# MacroBoard.net
KiCad netlist of a schematic drawn in EAGLE
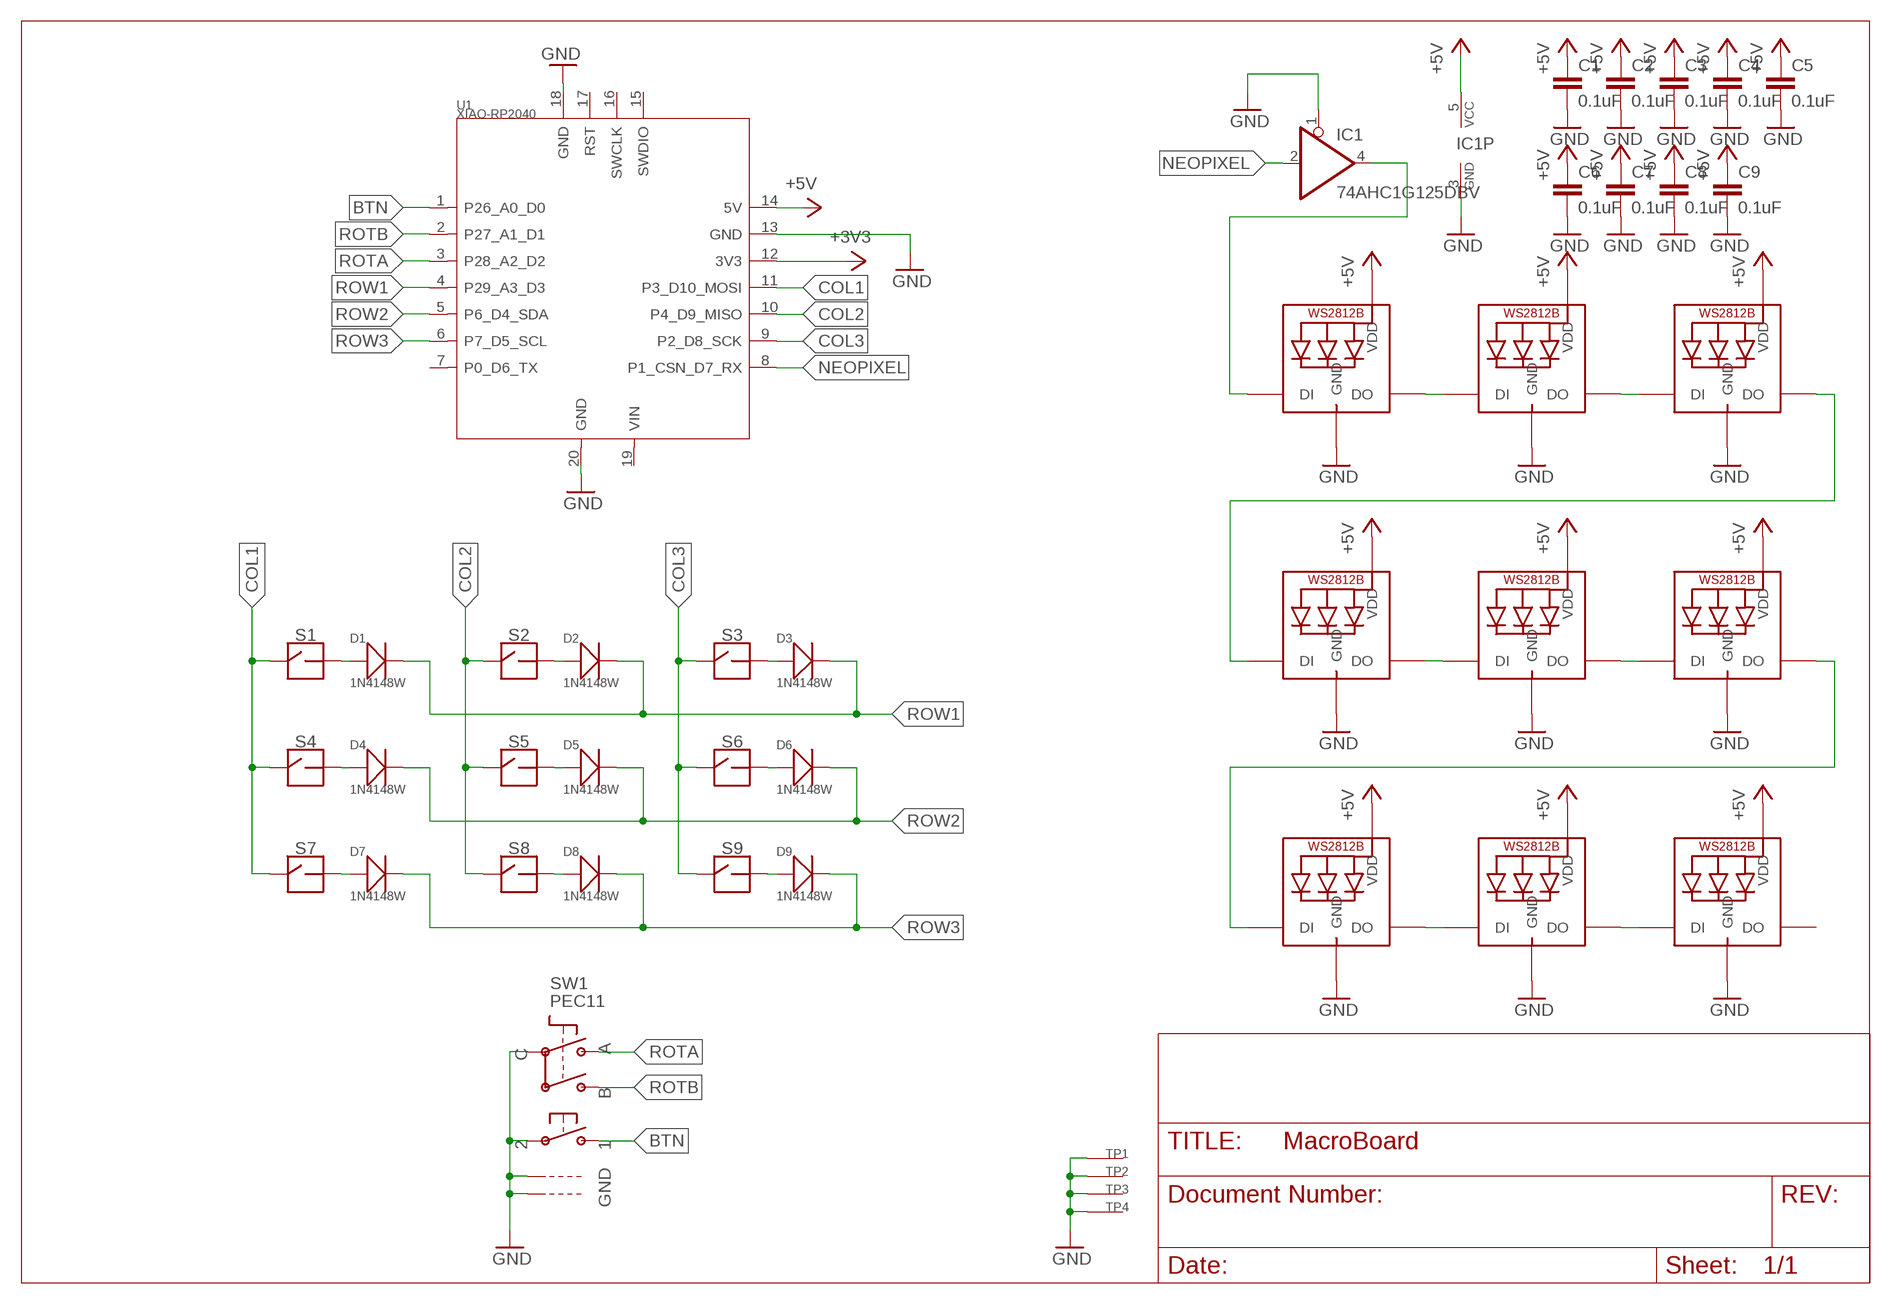
[diagram p0: schematic, sheet 1]

(export (version "E")
  (design (tool "Eeschema 10.0.6"))
  (components
    (comp (ref "C1")
      (value "0.1uF")
      (footprint "eagle-import:C0805K")
      (libsource (lib "eagle-import") (part "C-EUC0805K"))
    )
    (comp (ref "C2")
      (value "0.1uF")
      (footprint "eagle-import:C0805K")
      (libsource (lib "eagle-import") (part "C-EUC0805K"))
    )
    (comp (ref "C3")
      (value "0.1uF")
      (footprint "eagle-import:C0805K")
      (libsource (lib "eagle-import") (part "C-EUC0805K"))
    )
    (comp (ref "C4")
      (value "0.1uF")
      (footprint "eagle-import:C0805K")
      (libsource (lib "eagle-import") (part "C-EUC0805K"))
    )
    (comp (ref "C5")
      (value "0.1uF")
      (footprint "eagle-import:C0805K")
      (libsource (lib "eagle-import") (part "C-EUC0805K"))
    )
    (comp (ref "C6")
      (value "0.1uF")
      (footprint "eagle-import:C0805K")
      (libsource (lib "eagle-import") (part "C-EUC0805K"))
    )
    (comp (ref "C7")
      (value "0.1uF")
      (footprint "eagle-import:C0805K")
      (libsource (lib "eagle-import") (part "C-EUC0805K"))
    )
    (comp (ref "C8")
      (value "0.1uF")
      (footprint "eagle-import:C0805K")
      (libsource (lib "eagle-import") (part "C-EUC0805K"))
    )
    (comp (ref "C9")
      (value "0.1uF")
      (footprint "eagle-import:C0805K")
      (libsource (lib "eagle-import") (part "C-EUC0805K"))
    )
    (comp (ref "D1")
      (value "1N4148W")
      (footprint "eagle-import:SOD-123")
      (fields (field (name "MPN") "B5819W"))
      (libsource (lib "eagle-import") (part "SMD-DIODE-SCHOTTKY-20V-1A(SOD-123)"))
    )
    (comp (ref "D2")
      (value "1N4148W")
      (footprint "eagle-import:SOD-123")
      (fields (field (name "MPN") "B5819W"))
      (libsource (lib "eagle-import") (part "SMD-DIODE-SCHOTTKY-20V-1A(SOD-123)"))
    )
    (comp (ref "D3")
      (value "1N4148W")
      (footprint "eagle-import:SOD-123")
      (fields (field (name "MPN") "B5819W"))
      (libsource (lib "eagle-import") (part "SMD-DIODE-SCHOTTKY-20V-1A(SOD-123)"))
    )
    (comp (ref "D4")
      (value "1N4148W")
      (footprint "eagle-import:SOD-123")
      (fields (field (name "MPN") "B5819W"))
      (libsource (lib "eagle-import") (part "SMD-DIODE-SCHOTTKY-20V-1A(SOD-123)"))
    )
    (comp (ref "D5")
      (value "1N4148W")
      (footprint "eagle-import:SOD-123")
      (fields (field (name "MPN") "B5819W"))
      (libsource (lib "eagle-import") (part "SMD-DIODE-SCHOTTKY-20V-1A(SOD-123)"))
    )
    (comp (ref "D6")
      (value "1N4148W")
      (footprint "eagle-import:SOD-123")
      (fields (field (name "MPN") "B5819W"))
      (libsource (lib "eagle-import") (part "SMD-DIODE-SCHOTTKY-20V-1A(SOD-123)"))
    )
    (comp (ref "D7")
      (value "1N4148W")
      (footprint "eagle-import:SOD-123")
      (fields (field (name "MPN") "B5819W"))
      (libsource (lib "eagle-import") (part "SMD-DIODE-SCHOTTKY-20V-1A(SOD-123)"))
    )
    (comp (ref "D8")
      (value "1N4148W")
      (footprint "eagle-import:SOD-123")
      (fields (field (name "MPN") "B5819W"))
      (libsource (lib "eagle-import") (part "SMD-DIODE-SCHOTTKY-20V-1A(SOD-123)"))
    )
    (comp (ref "D9")
      (value "1N4148W")
      (footprint "eagle-import:SOD-123")
      (fields (field (name "MPN") "B5819W"))
      (libsource (lib "eagle-import") (part "SMD-DIODE-SCHOTTKY-20V-1A(SOD-123)"))
    )
    (comp (ref "IC1")
      (value "74AHC1G125DBV")
      (footprint "eagle-import:SOT23-5")
      (fields (field (name "SPICEPREFIX") "J"))
      (libsource (lib "eagle-import") (part "741G125DBVAHC"))
    )
    (comp (ref "LED1")
      (value "WS2812B_SK6812E")
      (footprint "eagle-import:NEO3535_REVERSE")
      (libsource (lib "eagle-import") (part "WS2812B_SK6812E"))
    )
    (comp (ref "LED2")
      (value "WS2812B_SK6812E")
      (footprint "eagle-import:NEO3535_REVERSE")
      (libsource (lib "eagle-import") (part "WS2812B_SK6812E"))
    )
    (comp (ref "LED3")
      (value "WS2812B_SK6812E")
      (footprint "eagle-import:NEO3535_REVERSE")
      (libsource (lib "eagle-import") (part "WS2812B_SK6812E"))
    )
    (comp (ref "LED4")
      (value "WS2812B_SK6812E")
      (footprint "eagle-import:NEO3535_REVERSE")
      (libsource (lib "eagle-import") (part "WS2812B_SK6812E"))
    )
    (comp (ref "LED5")
      (value "WS2812B_SK6812E")
      (footprint "eagle-import:NEO3535_REVERSE")
      (libsource (lib "eagle-import") (part "WS2812B_SK6812E"))
    )
    (comp (ref "LED6")
      (value "WS2812B_SK6812E")
      (footprint "eagle-import:NEO3535_REVERSE")
      (libsource (lib "eagle-import") (part "WS2812B_SK6812E"))
    )
    (comp (ref "LED7")
      (value "WS2812B_SK6812E")
      (footprint "eagle-import:NEO3535_REVERSE")
      (libsource (lib "eagle-import") (part "WS2812B_SK6812E"))
    )
    (comp (ref "LED8")
      (value "WS2812B_SK6812E")
      (footprint "eagle-import:NEO3535_REVERSE")
      (libsource (lib "eagle-import") (part "WS2812B_SK6812E"))
    )
    (comp (ref "LED9")
      (value "WS2812B_SK6812E")
      (footprint "eagle-import:NEO3535_REVERSE")
      (libsource (lib "eagle-import") (part "WS2812B_SK6812E"))
    )
    (comp (ref "S1")
      (value "SOCKET")
      (footprint "eagle-import:KAILH_SOCKET")
      (libsource (lib "eagle-import") (part "KBD_SWITCH_KAILH_SOCKETBOX_JADE_KAILH_SOCKET"))
    )
    (comp (ref "S2")
      (value "SOCKET")
      (footprint "eagle-import:KAILH_SOCKET")
      (libsource (lib "eagle-import") (part "KBD_SWITCH_KAILH_SOCKETBOX_JADE_KAILH_SOCKET"))
    )
    (comp (ref "S3")
      (value "SOCKET")
      (footprint "eagle-import:KAILH_SOCKET")
      (libsource (lib "eagle-import") (part "KBD_SWITCH_KAILH_SOCKETBOX_JADE_KAILH_SOCKET"))
    )
    (comp (ref "S4")
      (value "SOCKET")
      (footprint "eagle-import:KAILH_SOCKET")
      (libsource (lib "eagle-import") (part "KBD_SWITCH_KAILH_SOCKETBOX_JADE_KAILH_SOCKET"))
    )
    (comp (ref "S5")
      (value "SOCKET")
      (footprint "eagle-import:KAILH_SOCKET")
      (libsource (lib "eagle-import") (part "KBD_SWITCH_KAILH_SOCKETBOX_JADE_KAILH_SOCKET"))
    )
    (comp (ref "S6")
      (value "SOCKET")
      (footprint "eagle-import:KAILH_SOCKET")
      (libsource (lib "eagle-import") (part "KBD_SWITCH_KAILH_SOCKETBOX_JADE_KAILH_SOCKET"))
    )
    (comp (ref "S7")
      (value "SOCKET")
      (footprint "eagle-import:KAILH_SOCKET")
      (libsource (lib "eagle-import") (part "KBD_SWITCH_KAILH_SOCKETBOX_JADE_KAILH_SOCKET"))
    )
    (comp (ref "S8")
      (value "SOCKET")
      (footprint "eagle-import:KAILH_SOCKET")
      (libsource (lib "eagle-import") (part "KBD_SWITCH_KAILH_SOCKETBOX_JADE_KAILH_SOCKET"))
    )
    (comp (ref "S9")
      (value "SOCKET")
      (footprint "eagle-import:KAILH_SOCKET")
      (libsource (lib "eagle-import") (part "KBD_SWITCH_KAILH_SOCKETBOX_JADE_KAILH_SOCKET"))
    )
    (comp (ref "SW1")
      (value "PEC11")
      (footprint "eagle-import:PEC11+SWITCH")
      (libsource (lib "eagle-import") (part "ENCODER_PLUS_SWITCH_PEC11_BOURNS"))
    )
    (comp (ref "TP1")
      (value "SEWTAP_SMTNUTM3")
      (footprint "eagle-import:SMT_NUT_3MM")
      (libsource (lib "eagle-import") (part "SEWTAP_SMTNUTM3"))
    )
    (comp (ref "TP2")
      (value "SEWTAP_SMTNUTM3")
      (footprint "eagle-import:SMT_NUT_3MM")
      (libsource (lib "eagle-import") (part "SEWTAP_SMTNUTM3"))
    )
    (comp (ref "TP3")
      (value "SEWTAP_SMTNUTM3")
      (footprint "eagle-import:SMT_NUT_3MM")
      (libsource (lib "eagle-import") (part "SEWTAP_SMTNUTM3"))
    )
    (comp (ref "TP4")
      (value "SEWTAP_SMTNUTM3")
      (footprint "eagle-import:SMT_NUT_3MM")
      (libsource (lib "eagle-import") (part "SEWTAP_SMTNUTM3"))
    )
    (comp (ref "U1")
      (value "XIAO-RP2040")
      (footprint "eagle-import:XIAO-SAMD21_RP2040-MODULE14P-2.54-21X17.8MM")
      (libsource (lib "eagle-import") (part "XIAO-RP2040"))
    )
  )
  (nets
    (net (code "1") (name "+3V3") (class "Default")
      (node (ref "U1") (pin "12") (pinfunction "3V3_12") (pintype "bidirectional"))
    )
    (net (code "2") (name "+5V") (class "Default")
      (node (ref "C1") (pin "1") (pinfunction "1_1") (pintype "passive"))
      (node (ref "C2") (pin "1") (pinfunction "1_1") (pintype "passive"))
      (node (ref "C3") (pin "1") (pinfunction "1_1") (pintype "passive"))
      (node (ref "C4") (pin "1") (pinfunction "1_1") (pintype "passive"))
      (node (ref "C5") (pin "1") (pinfunction "1_1") (pintype "passive"))
      (node (ref "C6") (pin "1") (pinfunction "1_1") (pintype "passive"))
      (node (ref "C7") (pin "1") (pinfunction "1_1") (pintype "passive"))
      (node (ref "C8") (pin "1") (pinfunction "1_1") (pintype "passive"))
      (node (ref "C9") (pin "1") (pinfunction "1_1") (pintype "passive"))
      (node (ref "IC1") (pin "5") (pinfunction "VCC_5") (pintype "power_in"))
      (node (ref "LED1") (pin "1-VDD") (pinfunction "VDD_1-VDD") (pintype "power_in"))
      (node (ref "LED2") (pin "1-VDD") (pinfunction "VDD_1-VDD") (pintype "power_in"))
      (node (ref "LED3") (pin "1-VDD") (pinfunction "VDD_1-VDD") (pintype "power_in"))
      (node (ref "LED4") (pin "1-VDD") (pinfunction "VDD_1-VDD") (pintype "power_in"))
      (node (ref "LED5") (pin "1-VDD") (pinfunction "VDD_1-VDD") (pintype "power_in"))
      (node (ref "LED6") (pin "1-VDD") (pinfunction "VDD_1-VDD") (pintype "power_in"))
      (node (ref "LED7") (pin "1-VDD") (pinfunction "VDD_1-VDD") (pintype "power_in"))
      (node (ref "LED8") (pin "1-VDD") (pinfunction "VDD_1-VDD") (pintype "power_in"))
      (node (ref "LED9") (pin "1-VDD") (pinfunction "VDD_1-VDD") (pintype "power_in"))
      (node (ref "U1") (pin "14") (pinfunction "5V_14") (pintype "bidirectional"))
    )
    (net (code "3") (name "BTN") (class "Default")
      (node (ref "SW1") (pin "P$1") (pinfunction "P$1_P$1") (pintype "passive"))
      (node (ref "U1") (pin "1") (pinfunction "P26_A0_D0_1") (pintype "bidirectional"))
    )
    (net (code "4") (name "COL1") (class "Default")
      (node (ref "S1") (pin "1") (pinfunction "1_1") (pintype "passive"))
      (node (ref "S4") (pin "1") (pinfunction "1_1") (pintype "passive"))
      (node (ref "S7") (pin "1") (pinfunction "1_1") (pintype "passive"))
      (node (ref "U1") (pin "11") (pinfunction "P3_D10_MOSI_11") (pintype "bidirectional"))
    )
    (net (code "5") (name "COL2") (class "Default")
      (node (ref "S2") (pin "1") (pinfunction "1_1") (pintype "passive"))
      (node (ref "S5") (pin "1") (pinfunction "1_1") (pintype "passive"))
      (node (ref "S8") (pin "1") (pinfunction "1_1") (pintype "passive"))
      (node (ref "U1") (pin "10") (pinfunction "P4_D9_MISO_10") (pintype "bidirectional"))
    )
    (net (code "6") (name "COL3") (class "Default")
      (node (ref "S3") (pin "1") (pinfunction "1_1") (pintype "passive"))
      (node (ref "S6") (pin "1") (pinfunction "1_1") (pintype "passive"))
      (node (ref "S9") (pin "1") (pinfunction "1_1") (pintype "passive"))
      (node (ref "U1") (pin "9") (pinfunction "P2_D8_SCK_9") (pintype "bidirectional"))
    )
    (net (code "7") (name "GND") (class "Default")
      (node (ref "C1") (pin "2") (pinfunction "2_2") (pintype "passive"))
      (node (ref "C2") (pin "2") (pinfunction "2_2") (pintype "passive"))
      (node (ref "C3") (pin "2") (pinfunction "2_2") (pintype "passive"))
      (node (ref "C4") (pin "2") (pinfunction "2_2") (pintype "passive"))
      (node (ref "C5") (pin "2") (pinfunction "2_2") (pintype "passive"))
      (node (ref "C6") (pin "2") (pinfunction "2_2") (pintype "passive"))
      (node (ref "C7") (pin "2") (pinfunction "2_2") (pintype "passive"))
      (node (ref "C8") (pin "2") (pinfunction "2_2") (pintype "passive"))
      (node (ref "C9") (pin "2") (pinfunction "2_2") (pintype "passive"))
      (node (ref "IC1") (pin "1") (pinfunction "OE_1") (pintype "input"))
      (node (ref "IC1") (pin "3") (pinfunction "GND_3") (pintype "power_in"))
      (node (ref "LED1") (pin "3-GND") (pinfunction "GND_3-GND") (pintype "power_in"))
      (node (ref "LED2") (pin "3-GND") (pinfunction "GND_3-GND") (pintype "power_in"))
      (node (ref "LED3") (pin "3-GND") (pinfunction "GND_3-GND") (pintype "power_in"))
      (node (ref "LED4") (pin "3-GND") (pinfunction "GND_3-GND") (pintype "power_in"))
      (node (ref "LED5") (pin "3-GND") (pinfunction "GND_3-GND") (pintype "power_in"))
      (node (ref "LED6") (pin "3-GND") (pinfunction "GND_3-GND") (pintype "power_in"))
      (node (ref "LED7") (pin "3-GND") (pinfunction "GND_3-GND") (pintype "power_in"))
      (node (ref "LED8") (pin "3-GND") (pinfunction "GND_3-GND") (pintype "power_in"))
      (node (ref "LED9") (pin "3-GND") (pinfunction "GND_3-GND") (pintype "power_in"))
      (node (ref "SW1") (pin "P$2") (pinfunction "P$2_P$2") (pintype "passive"))
      (node (ref "SW1") (pin "P$C") (pinfunction "P$C_P$C") (pintype "passive"))
      (node (ref "SW1") (pin "P$GND1") (pinfunction "P$GND1_P$GND1") (pintype "passive"))
      (node (ref "SW1") (pin "P$GND2") (pinfunction "P$GND2_P$GND2") (pintype "passive"))
      (node (ref "TP1") (pin "P$1") (pinfunction "SEW_P$1") (pintype "bidirectional"))
      (node (ref "TP2") (pin "P$1") (pinfunction "SEW_P$1") (pintype "bidirectional"))
      (node (ref "TP3") (pin "P$1") (pinfunction "SEW_P$1") (pintype "bidirectional"))
      (node (ref "TP4") (pin "P$1") (pinfunction "SEW_P$1") (pintype "bidirectional"))
      (node (ref "U1") (pin "13") (pinfunction "GND_13") (pintype "bidirectional"))
      (node (ref "U1") (pin "18") (pinfunction "GND_18") (pintype "bidirectional"))
      (node (ref "U1") (pin "20") (pinfunction "GND_20") (pintype "bidirectional"))
    )
    (net (code "8") (name "NEOPIXEL") (class "Default")
      (node (ref "IC1") (pin "2") (pinfunction "I_2") (pintype "input"))
      (node (ref "U1") (pin "8") (pinfunction "P1_CSN_D7_RX_8") (pintype "bidirectional"))
    )
    (net (code "9") (name "Net-(D1-Pad+)") (class "Default")
      (node (ref "D1") (pin "+") (pinfunction "+_+") (pintype "passive"))
      (node (ref "S1") (pin "2") (pinfunction "2_2") (pintype "passive"))
    )
    (net (code "10") (name "Net-(D2-Pad+)") (class "Default")
      (node (ref "D2") (pin "+") (pinfunction "+_+") (pintype "passive"))
      (node (ref "S2") (pin "2") (pinfunction "2_2") (pintype "passive"))
    )
    (net (code "11") (name "Net-(D3-Pad+)") (class "Default")
      (node (ref "D3") (pin "+") (pinfunction "+_+") (pintype "passive"))
      (node (ref "S3") (pin "2") (pinfunction "2_2") (pintype "passive"))
    )
    (net (code "12") (name "Net-(D4-Pad+)") (class "Default")
      (node (ref "D4") (pin "+") (pinfunction "+_+") (pintype "passive"))
      (node (ref "S4") (pin "2") (pinfunction "2_2") (pintype "passive"))
    )
    (net (code "13") (name "Net-(D5-Pad+)") (class "Default")
      (node (ref "D5") (pin "+") (pinfunction "+_+") (pintype "passive"))
      (node (ref "S5") (pin "2") (pinfunction "2_2") (pintype "passive"))
    )
    (net (code "14") (name "Net-(D6-Pad+)") (class "Default")
      (node (ref "D6") (pin "+") (pinfunction "+_+") (pintype "passive"))
      (node (ref "S6") (pin "2") (pinfunction "2_2") (pintype "passive"))
    )
    (net (code "15") (name "Net-(D7-Pad+)") (class "Default")
      (node (ref "D7") (pin "+") (pinfunction "+_+") (pintype "passive"))
      (node (ref "S7") (pin "2") (pinfunction "2_2") (pintype "passive"))
    )
    (net (code "16") (name "Net-(D8-Pad+)") (class "Default")
      (node (ref "D8") (pin "+") (pinfunction "+_+") (pintype "passive"))
      (node (ref "S8") (pin "2") (pinfunction "2_2") (pintype "passive"))
    )
    (net (code "17") (name "Net-(D9-Pad+)") (class "Default")
      (node (ref "D9") (pin "+") (pinfunction "+_+") (pintype "passive"))
      (node (ref "S9") (pin "2") (pinfunction "2_2") (pintype "passive"))
    )
    (net (code "18") (name "Net-(IC1A-O)") (class "Default")
      (node (ref "IC1") (pin "4") (pinfunction "O_4") (pintype "tri_state"))
      (node (ref "LED1") (pin "4-DIN") (pinfunction "DI_4-DIN") (pintype "input"))
    )
    (net (code "19") (name "Net-(LED1-DO)") (class "Default")
      (node (ref "LED1") (pin "2-DOUT") (pinfunction "DO_2-DOUT") (pintype "output"))
      (node (ref "LED2") (pin "4-DIN") (pinfunction "DI_4-DIN") (pintype "input"))
    )
    (net (code "20") (name "Net-(LED2-DO)") (class "Default")
      (node (ref "LED2") (pin "2-DOUT") (pinfunction "DO_2-DOUT") (pintype "output"))
      (node (ref "LED3") (pin "4-DIN") (pinfunction "DI_4-DIN") (pintype "input"))
    )
    (net (code "21") (name "Net-(LED3-DO)") (class "Default")
      (node (ref "LED3") (pin "2-DOUT") (pinfunction "DO_2-DOUT") (pintype "output"))
      (node (ref "LED4") (pin "4-DIN") (pinfunction "DI_4-DIN") (pintype "input"))
    )
    (net (code "22") (name "Net-(LED4-DO)") (class "Default")
      (node (ref "LED4") (pin "2-DOUT") (pinfunction "DO_2-DOUT") (pintype "output"))
      (node (ref "LED5") (pin "4-DIN") (pinfunction "DI_4-DIN") (pintype "input"))
    )
    (net (code "23") (name "Net-(LED5-DO)") (class "Default")
      (node (ref "LED5") (pin "2-DOUT") (pinfunction "DO_2-DOUT") (pintype "output"))
      (node (ref "LED6") (pin "4-DIN") (pinfunction "DI_4-DIN") (pintype "input"))
    )
    (net (code "24") (name "Net-(LED6-DO)") (class "Default")
      (node (ref "LED6") (pin "2-DOUT") (pinfunction "DO_2-DOUT") (pintype "output"))
      (node (ref "LED7") (pin "4-DIN") (pinfunction "DI_4-DIN") (pintype "input"))
    )
    (net (code "25") (name "Net-(LED7-DO)") (class "Default")
      (node (ref "LED7") (pin "2-DOUT") (pinfunction "DO_2-DOUT") (pintype "output"))
      (node (ref "LED8") (pin "4-DIN") (pinfunction "DI_4-DIN") (pintype "input"))
    )
    (net (code "26") (name "Net-(LED8-DO)") (class "Default")
      (node (ref "LED8") (pin "2-DOUT") (pinfunction "DO_2-DOUT") (pintype "output"))
      (node (ref "LED9") (pin "4-DIN") (pinfunction "DI_4-DIN") (pintype "input"))
    )
    (net (code "27") (name "ROTA") (class "Default")
      (node (ref "SW1") (pin "P$A") (pinfunction "P$A_P$A") (pintype "passive"))
      (node (ref "U1") (pin "3") (pinfunction "P28_A2_D2_3") (pintype "bidirectional"))
    )
    (net (code "28") (name "ROTB") (class "Default")
      (node (ref "SW1") (pin "P$B") (pinfunction "P$B_P$B") (pintype "passive"))
      (node (ref "U1") (pin "2") (pinfunction "P27_A1_D1_2") (pintype "bidirectional"))
    )
    (net (code "29") (name "ROW1") (class "Default")
      (node (ref "D1") (pin "-") (pinfunction "-_-") (pintype "passive"))
      (node (ref "D2") (pin "-") (pinfunction "-_-") (pintype "passive"))
      (node (ref "D3") (pin "-") (pinfunction "-_-") (pintype "passive"))
      (node (ref "U1") (pin "4") (pinfunction "P29_A3_D3_4") (pintype "bidirectional"))
    )
    (net (code "30") (name "ROW2") (class "Default")
      (node (ref "D4") (pin "-") (pinfunction "-_-") (pintype "passive"))
      (node (ref "D5") (pin "-") (pinfunction "-_-") (pintype "passive"))
      (node (ref "D6") (pin "-") (pinfunction "-_-") (pintype "passive"))
      (node (ref "U1") (pin "5") (pinfunction "P6_D4_SDA_5") (pintype "bidirectional"))
    )
    (net (code "31") (name "ROW3") (class "Default")
      (node (ref "D7") (pin "-") (pinfunction "-_-") (pintype "passive"))
      (node (ref "D8") (pin "-") (pinfunction "-_-") (pintype "passive"))
      (node (ref "D9") (pin "-") (pinfunction "-_-") (pintype "passive"))
      (node (ref "U1") (pin "6") (pinfunction "P7_D5_SCL_6") (pintype "bidirectional"))
    )
    (net (code "32") (name "unconnected-(LED9-DO-Pad2-DOUT)") (class "Default")
      (node (ref "LED9") (pin "2-DOUT") (pinfunction "DO_2-DOUT") (pintype "output"))
    )
    (net (code "33") (name "unconnected-(U1-P0_D6_TX-Pad7)") (class "Default")
      (node (ref "U1") (pin "7") (pinfunction "P0_D6_TX_7") (pintype "bidirectional"))
    )
    (net (code "34") (name "unconnected-(U1-RST-Pad17)") (class "Default")
      (node (ref "U1") (pin "17") (pinfunction "RST_17") (pintype "bidirectional"))
    )
    (net (code "35") (name "unconnected-(U1-SWCLK-Pad16)") (class "Default")
      (node (ref "U1") (pin "16") (pinfunction "SWCLK_16") (pintype "bidirectional"))
    )
    (net (code "36") (name "unconnected-(U1-SWDIO-Pad15)") (class "Default")
      (node (ref "U1") (pin "15") (pinfunction "SWDIO_15") (pintype "bidirectional"))
    )
    (net (code "37") (name "unconnected-(U1-VIN-Pad19)") (class "Default")
      (node (ref "U1") (pin "19") (pinfunction "VIN_19") (pintype "bidirectional"))
    )
  )
)
